# pull_up_pull_down_switch.net
KiCad netlist of a schematic drawn in Altium Designer
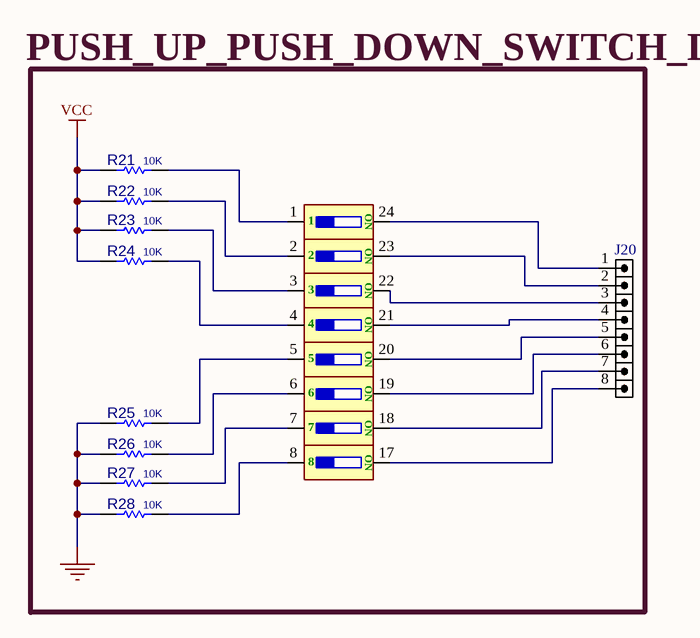
[diagram p0: pull_up_pull_down_switch.SchDoc]

(export (version "E")
  (design (tool "Eeschema 10.0.6"))
  (components
    (comp (ref "J20")
      (value "HDR1X8")
      (footprint "HDR_M_1X8")
      (description "CONN, HEADER, Male, pitch: 2.54mm, 8POS")
      (libsource (lib "conn_header_2.54mm_st") (part "HDR_M_1X8"))
    )
    (comp (ref "R21")
      (value "10K")
      (footprint "R025W_AX04")
      (description "RESISTOR, THD")
      (fields (field (name "MANF_P#") "RK73H1ETTP4701F") (field (name "MANF") "KOA SPEER"))
      (libsource (lib "passive_thd") (part "RES_THD"))
    )
    (comp (ref "R22")
      (value "10K")
      (footprint "R025W_AX04")
      (description "RESISTOR, THD")
      (fields (field (name "MANF_P#") "RK73H1ETTP4701F") (field (name "MANF") "KOA SPEER"))
      (libsource (lib "passive_thd") (part "RES_THD"))
    )
    (comp (ref "R23")
      (value "10K")
      (footprint "R025W_AX04")
      (description "RESISTOR, THD")
      (fields (field (name "MANF_P#") "RK73H1ETTP4701F") (field (name "MANF") "KOA SPEER"))
      (libsource (lib "passive_thd") (part "RES_THD"))
    )
    (comp (ref "R24")
      (value "10K")
      (footprint "R025W_AX04")
      (description "RESISTOR, THD")
      (fields (field (name "MANF_P#") "RK73H1ETTP4701F") (field (name "MANF") "KOA SPEER"))
      (libsource (lib "passive_thd") (part "RES_THD"))
    )
    (comp (ref "R25")
      (value "10K")
      (footprint "R025W_AX04")
      (description "RESISTOR, THD")
      (fields (field (name "MANF_P#") "RK73H1ETTP4701F") (field (name "MANF") "KOA SPEER"))
      (libsource (lib "passive_thd") (part "RES_THD"))
    )
    (comp (ref "R26")
      (value "10K")
      (footprint "R025W_AX04")
      (description "RESISTOR, THD")
      (fields (field (name "MANF_P#") "RK73H1ETTP4701F") (field (name "MANF") "KOA SPEER"))
      (libsource (lib "passive_thd") (part "RES_THD"))
    )
    (comp (ref "R27")
      (value "10K")
      (footprint "R025W_AX04")
      (description "RESISTOR, THD")
      (fields (field (name "MANF_P#") "RK73H1ETTP4701F") (field (name "MANF") "KOA SPEER"))
      (libsource (lib "passive_thd") (part "RES_THD"))
    )
    (comp (ref "R28")
      (value "10K")
      (footprint "R025W_AX04")
      (description "RESISTOR, THD")
      (fields (field (name "MANF_P#") "RK73H1ETTP4701F") (field (name "MANF") "KOA SPEER"))
      (libsource (lib "passive_thd") (part "RES_THD"))
    )
    (comp (ref "S2")
      (value "DIPSW12")
      (footprint "DIPSW254T_12")
      (description "SWITCH, DIP, 12P, THD")
      (fields (field (name "MANF") "MANF") (field (name "MANF_P#") "MANF_P#"))
      (libsource (lib "switch_dip") (part "DIPSW254T_12P"))
    )
  )
  (nets
    (net (code "1") (name "GND") (class "Default")
      (node (ref "R25") (pin "2") (pinfunction "2_2") (pintype "passive"))
      (node (ref "R26") (pin "2") (pinfunction "2_2") (pintype "passive"))
      (node (ref "R27") (pin "2") (pinfunction "2_2") (pintype "passive"))
      (node (ref "R28") (pin "2") (pinfunction "2_2") (pintype "passive"))
    )
    (net (code "2") (name "Net-(S2A-A1)") (class "Default")
      (node (ref "R21") (pin "1") (pinfunction "1_1") (pintype "passive"))
      (node (ref "S2") (pin "1") (pinfunction "A1_1") (pintype "passive"))
    )
    (net (code "3") (name "Net-(S2A-B1)") (class "Default")
      (node (ref "J20") (pin "1") (pinfunction "1_1") (pintype "passive"))
      (node (ref "S2") (pin "24") (pinfunction "B1_24") (pintype "passive"))
    )
    (net (code "4") (name "Net-(S2B-A2)") (class "Default")
      (node (ref "R22") (pin "1") (pinfunction "1_1") (pintype "passive"))
      (node (ref "S2") (pin "2") (pinfunction "A2_2") (pintype "passive"))
    )
    (net (code "5") (name "Net-(S2B-B2)") (class "Default")
      (node (ref "J20") (pin "2") (pinfunction "2_2") (pintype "passive"))
      (node (ref "S2") (pin "23") (pinfunction "B2_23") (pintype "passive"))
    )
    (net (code "6") (name "Net-(S2C-A3)") (class "Default")
      (node (ref "R23") (pin "1") (pinfunction "1_1") (pintype "passive"))
      (node (ref "S2") (pin "3") (pinfunction "A3_3") (pintype "passive"))
    )
    (net (code "7") (name "Net-(S2C-B3)") (class "Default")
      (node (ref "J20") (pin "3") (pinfunction "3_3") (pintype "passive"))
      (node (ref "S2") (pin "22") (pinfunction "B3_22") (pintype "passive"))
    )
    (net (code "8") (name "Net-(S2D-A4)") (class "Default")
      (node (ref "R24") (pin "1") (pinfunction "1_1") (pintype "passive"))
      (node (ref "S2") (pin "4") (pinfunction "A4_4") (pintype "passive"))
    )
    (net (code "9") (name "Net-(S2D-B4)") (class "Default")
      (node (ref "J20") (pin "4") (pinfunction "4_4") (pintype "passive"))
      (node (ref "S2") (pin "21") (pinfunction "B4_21") (pintype "passive"))
    )
    (net (code "10") (name "Net-(S2E-A5)") (class "Default")
      (node (ref "R25") (pin "1") (pinfunction "1_1") (pintype "passive"))
      (node (ref "S2") (pin "5") (pinfunction "A5_5") (pintype "passive"))
    )
    (net (code "11") (name "Net-(S2E-B5)") (class "Default")
      (node (ref "J20") (pin "5") (pinfunction "5_5") (pintype "passive"))
      (node (ref "S2") (pin "20") (pinfunction "B5_20") (pintype "passive"))
    )
    (net (code "12") (name "Net-(S2F-A6)") (class "Default")
      (node (ref "R26") (pin "1") (pinfunction "1_1") (pintype "passive"))
      (node (ref "S2") (pin "6") (pinfunction "A6_6") (pintype "passive"))
    )
    (net (code "13") (name "Net-(S2F-B6)") (class "Default")
      (node (ref "J20") (pin "6") (pinfunction "6_6") (pintype "passive"))
      (node (ref "S2") (pin "19") (pinfunction "B6_19") (pintype "passive"))
    )
    (net (code "14") (name "Net-(S2G-A7)") (class "Default")
      (node (ref "R27") (pin "1") (pinfunction "1_1") (pintype "passive"))
      (node (ref "S2") (pin "7") (pinfunction "A7_7") (pintype "passive"))
    )
    (net (code "15") (name "Net-(S2G-B7)") (class "Default")
      (node (ref "J20") (pin "7") (pinfunction "7_7") (pintype "passive"))
      (node (ref "S2") (pin "18") (pinfunction "B7_18") (pintype "passive"))
    )
    (net (code "16") (name "Net-(S2H-A8)") (class "Default")
      (node (ref "R28") (pin "1") (pinfunction "1_1") (pintype "passive"))
      (node (ref "S2") (pin "8") (pinfunction "A8_8") (pintype "passive"))
    )
    (net (code "17") (name "Net-(S2H-B8)") (class "Default")
      (node (ref "J20") (pin "8") (pinfunction "8_8") (pintype "passive"))
      (node (ref "S2") (pin "17") (pinfunction "B8_17") (pintype "passive"))
    )
    (net (code "18") (name "VCC") (class "Default")
      (node (ref "R21") (pin "2") (pinfunction "2_2") (pintype "passive"))
      (node (ref "R22") (pin "2") (pinfunction "2_2") (pintype "passive"))
      (node (ref "R23") (pin "2") (pinfunction "2_2") (pintype "passive"))
      (node (ref "R24") (pin "2") (pinfunction "2_2") (pintype "passive"))
    )
  )
)
